# Microcontroller_board_Photodiode_plate.net
KiCad netlist of a schematic drawn in EasyEDA
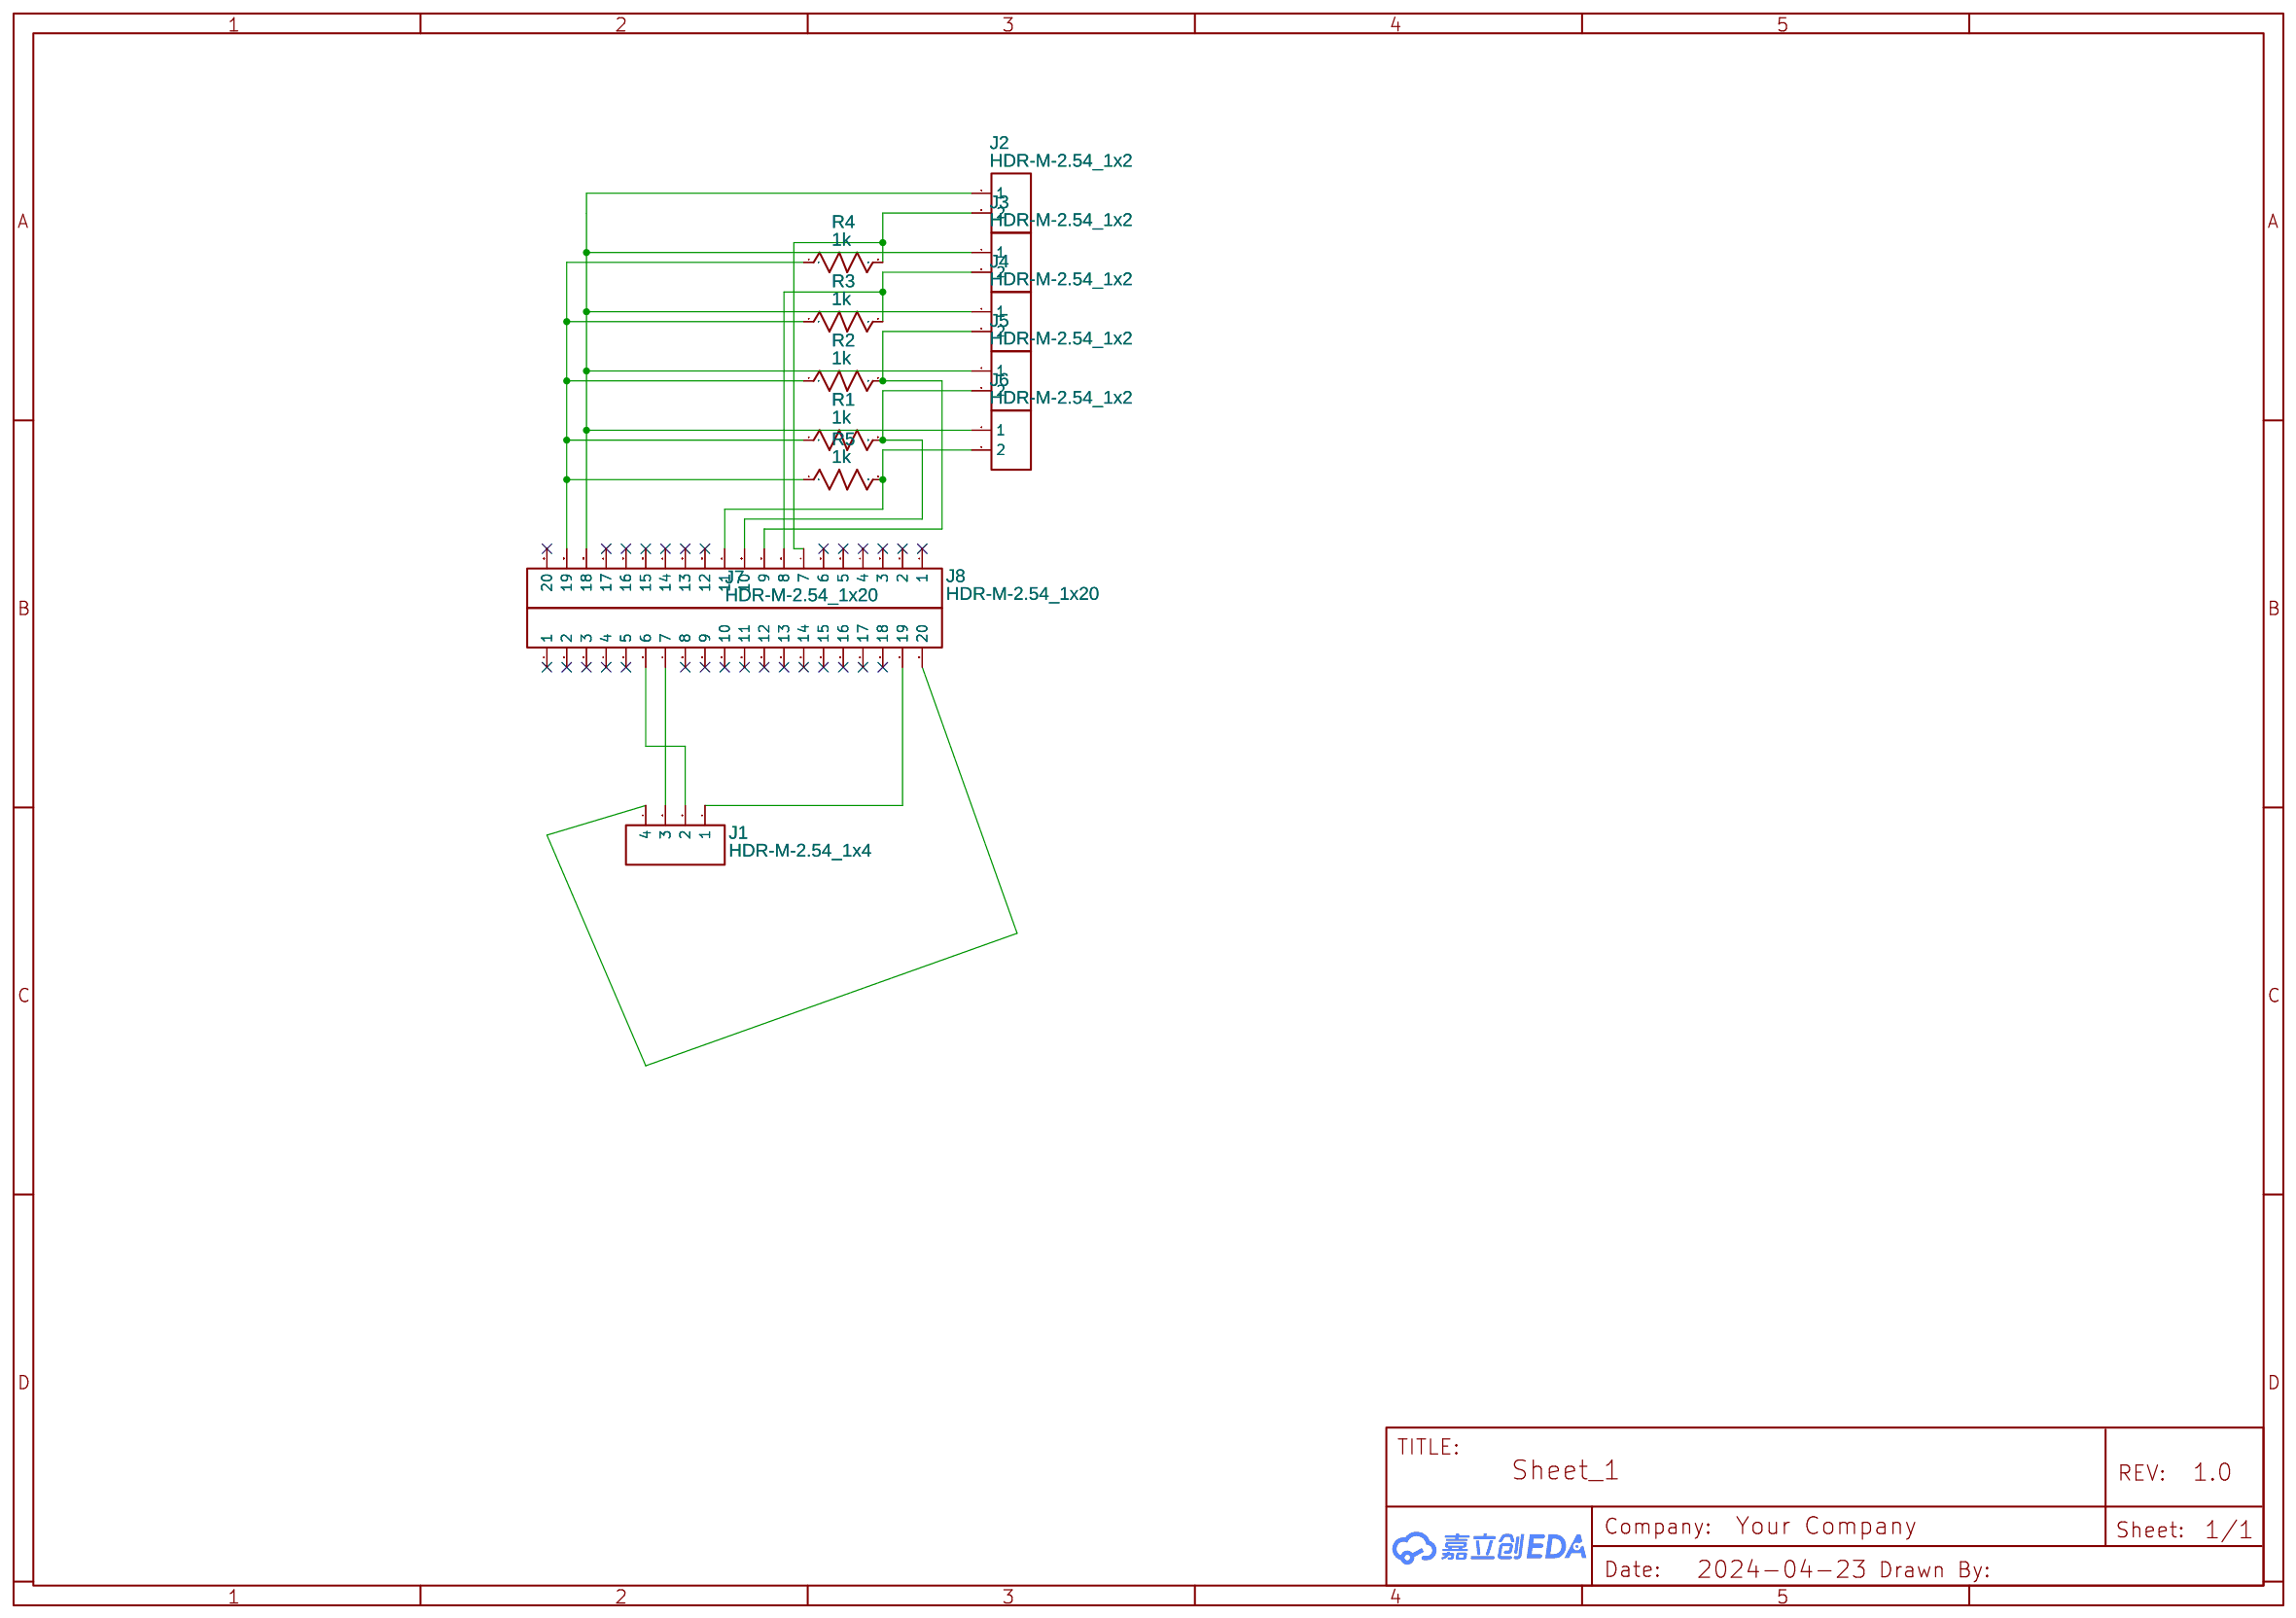
[diagram p0: schematic sheet]

(export (version "E")
  (design (tool "Eeschema 10.0.6"))
  (components
    (comp (ref "J1")
      (value "HDR-M-2.54_1x4")
      (fields (field (name "BOM_Supplier Part") "C124378"))
      (libsource (lib "") (part "HDR-M-2.54_1x4"))
    )
    (comp (ref "J2")
      (value "HDR-M-2.54_1x2")
      (fields (field (name "BOM_Supplier Part") "C124375"))
      (libsource (lib "") (part "HDR-M-2.54_1x2"))
    )
    (comp (ref "J3")
      (value "HDR-M-2.54_1x2")
      (fields (field (name "BOM_Supplier Part") "C124375"))
      (libsource (lib "") (part "HDR-M-2.54_1x2"))
    )
    (comp (ref "J4")
      (value "HDR-M-2.54_1x2")
      (fields (field (name "BOM_Supplier Part") "C124375"))
      (libsource (lib "") (part "HDR-M-2.54_1x2"))
    )
    (comp (ref "J5")
      (value "HDR-M-2.54_1x2")
      (fields (field (name "BOM_Supplier Part") "C124375"))
      (libsource (lib "") (part "HDR-M-2.54_1x2"))
    )
    (comp (ref "J6")
      (value "HDR-M-2.54_1x2")
      (fields (field (name "BOM_Supplier Part") "C124375"))
      (libsource (lib "") (part "HDR-M-2.54_1x2"))
    )
    (comp (ref "J7")
      (value "HDR-M-2.54_1x20")
      (fields (field (name "BOM_Supplier Part") "C50981"))
      (libsource (lib "") (part "HDR-M-2.54_1x20"))
    )
    (comp (ref "J8")
      (value "HDR-M-2.54_1x20")
      (fields (field (name "BOM_Supplier Part") "C50981"))
      (libsource (lib "") (part "HDR-M-2.54_1x20_1"))
    )
    (comp (ref "R1") (value "1k") (libsource (lib "") (part "R_AXIAL-0.4_US")))
    (comp (ref "R2") (value "1k") (libsource (lib "") (part "R_AXIAL-0.4_US")))
    (comp (ref "R3") (value "1k") (libsource (lib "") (part "R_AXIAL-0.4_US")))
    (comp (ref "R4") (value "1k") (libsource (lib "") (part "R_AXIAL-0.4_US")))
    (comp (ref "R5") (value "1k") (libsource (lib "") (part "R_AXIAL-0.4_US")))
  )
  (nets
    (net (code "1") (name "Net-(J1-Pad1)") (class "Default")
      (node (ref "J1") (pin "1") (pinfunction "1_1") (pintype "unspecified"))
      (node (ref "J7") (pin "19") (pinfunction "19_19") (pintype "unspecified"))
    )
    (net (code "2") (name "Net-(J1-Pad2)") (class "Default")
      (node (ref "J1") (pin "2") (pinfunction "2_2") (pintype "unspecified"))
      (node (ref "J7") (pin "6") (pinfunction "6_6") (pintype "unspecified"))
    )
    (net (code "3") (name "Net-(J1-Pad3)") (class "Default")
      (node (ref "J1") (pin "3") (pinfunction "3_3") (pintype "unspecified"))
      (node (ref "J7") (pin "7") (pinfunction "7_7") (pintype "unspecified"))
    )
    (net (code "4") (name "Net-(J1-Pad4)") (class "Default")
      (node (ref "J1") (pin "4") (pinfunction "4_4") (pintype "unspecified"))
      (node (ref "J7") (pin "20") (pinfunction "20_20") (pintype "unspecified"))
    )
    (net (code "5") (name "Net-(J2-Pad1)") (class "Default")
      (node (ref "J2") (pin "1") (pinfunction "1_1") (pintype "unspecified"))
      (node (ref "J3") (pin "1") (pinfunction "1_1") (pintype "unspecified"))
      (node (ref "J4") (pin "1") (pinfunction "1_1") (pintype "unspecified"))
      (node (ref "J5") (pin "1") (pinfunction "1_1") (pintype "unspecified"))
      (node (ref "J6") (pin "1") (pinfunction "1_1") (pintype "unspecified"))
      (node (ref "J8") (pin "18") (pinfunction "18_18") (pintype "unspecified"))
    )
    (net (code "6") (name "Net-(J2-Pad2)") (class "Default")
      (node (ref "J2") (pin "2") (pinfunction "2_2") (pintype "unspecified"))
      (node (ref "J8") (pin "7") (pinfunction "7_7") (pintype "unspecified"))
      (node (ref "R4") (pin "2") (pinfunction "2_2") (pintype "unspecified"))
    )
    (net (code "7") (name "Net-(J3-Pad2)") (class "Default")
      (node (ref "J3") (pin "2") (pinfunction "2_2") (pintype "unspecified"))
      (node (ref "J8") (pin "8") (pinfunction "8_8") (pintype "unspecified"))
      (node (ref "R3") (pin "2") (pinfunction "2_2") (pintype "unspecified"))
    )
    (net (code "8") (name "Net-(J4-Pad2)") (class "Default")
      (node (ref "J4") (pin "2") (pinfunction "2_2") (pintype "unspecified"))
      (node (ref "J8") (pin "9") (pinfunction "9_9") (pintype "unspecified"))
      (node (ref "R2") (pin "2") (pinfunction "2_2") (pintype "unspecified"))
    )
    (net (code "9") (name "Net-(J5-Pad2)") (class "Default")
      (node (ref "J5") (pin "2") (pinfunction "2_2") (pintype "unspecified"))
      (node (ref "J8") (pin "10") (pinfunction "10_10") (pintype "unspecified"))
      (node (ref "R1") (pin "2") (pinfunction "2_2") (pintype "unspecified"))
    )
    (net (code "10") (name "Net-(J6-Pad2)") (class "Default")
      (node (ref "J6") (pin "2") (pinfunction "2_2") (pintype "unspecified"))
      (node (ref "J8") (pin "11") (pinfunction "11_11") (pintype "unspecified"))
      (node (ref "R5") (pin "2") (pinfunction "2_2") (pintype "unspecified"))
    )
    (net (code "11") (name "Net-(J8-Pad19)") (class "Default")
      (node (ref "J8") (pin "19") (pinfunction "19_19") (pintype "unspecified"))
      (node (ref "R1") (pin "1") (pinfunction "1_1") (pintype "unspecified"))
      (node (ref "R2") (pin "1") (pinfunction "1_1") (pintype "unspecified"))
      (node (ref "R3") (pin "1") (pinfunction "1_1") (pintype "unspecified"))
      (node (ref "R4") (pin "1") (pinfunction "1_1") (pintype "unspecified"))
      (node (ref "R5") (pin "1") (pinfunction "1_1") (pintype "unspecified"))
    )
    (net (code "12") (name "unconnected-(J7-Pad1)") (class "Default")
      (node (ref "J7") (pin "1") (pinfunction "1_1") (pintype "unspecified+no_connect"))
    )
    (net (code "13") (name "unconnected-(J7-Pad2)") (class "Default")
      (node (ref "J7") (pin "2") (pinfunction "2_2") (pintype "unspecified+no_connect"))
    )
    (net (code "14") (name "unconnected-(J7-Pad3)") (class "Default")
      (node (ref "J7") (pin "3") (pinfunction "3_3") (pintype "unspecified+no_connect"))
    )
    (net (code "15") (name "unconnected-(J7-Pad4)") (class "Default")
      (node (ref "J7") (pin "4") (pinfunction "4_4") (pintype "unspecified+no_connect"))
    )
    (net (code "16") (name "unconnected-(J7-Pad5)") (class "Default")
      (node (ref "J7") (pin "5") (pinfunction "5_5") (pintype "unspecified+no_connect"))
    )
    (net (code "17") (name "unconnected-(J7-Pad8)") (class "Default")
      (node (ref "J7") (pin "8") (pinfunction "8_8") (pintype "unspecified+no_connect"))
    )
    (net (code "18") (name "unconnected-(J7-Pad9)") (class "Default")
      (node (ref "J7") (pin "9") (pinfunction "9_9") (pintype "unspecified+no_connect"))
    )
    (net (code "19") (name "unconnected-(J7-Pad10)") (class "Default")
      (node (ref "J7") (pin "10") (pinfunction "10_10") (pintype "unspecified+no_connect"))
    )
    (net (code "20") (name "unconnected-(J7-Pad11)") (class "Default")
      (node (ref "J7") (pin "11") (pinfunction "11_11") (pintype "unspecified+no_connect"))
    )
    (net (code "21") (name "unconnected-(J7-Pad12)") (class "Default")
      (node (ref "J7") (pin "12") (pinfunction "12_12") (pintype "unspecified+no_connect"))
    )
    (net (code "22") (name "unconnected-(J7-Pad13)") (class "Default")
      (node (ref "J7") (pin "13") (pinfunction "13_13") (pintype "unspecified+no_connect"))
    )
    (net (code "23") (name "unconnected-(J7-Pad14)") (class "Default")
      (node (ref "J7") (pin "14") (pinfunction "14_14") (pintype "unspecified+no_connect"))
    )
    (net (code "24") (name "unconnected-(J7-Pad15)") (class "Default")
      (node (ref "J7") (pin "15") (pinfunction "15_15") (pintype "unspecified+no_connect"))
    )
    (net (code "25") (name "unconnected-(J7-Pad16)") (class "Default")
      (node (ref "J7") (pin "16") (pinfunction "16_16") (pintype "unspecified+no_connect"))
    )
    (net (code "26") (name "unconnected-(J7-Pad17)") (class "Default")
      (node (ref "J7") (pin "17") (pinfunction "17_17") (pintype "unspecified+no_connect"))
    )
    (net (code "27") (name "unconnected-(J7-Pad18)") (class "Default")
      (node (ref "J7") (pin "18") (pinfunction "18_18") (pintype "unspecified+no_connect"))
    )
    (net (code "28") (name "unconnected-(J8-Pad1)") (class "Default")
      (node (ref "J8") (pin "1") (pinfunction "1_1") (pintype "unspecified+no_connect"))
    )
    (net (code "29") (name "unconnected-(J8-Pad2)") (class "Default")
      (node (ref "J8") (pin "2") (pinfunction "2_2") (pintype "unspecified+no_connect"))
    )
    (net (code "30") (name "unconnected-(J8-Pad3)") (class "Default")
      (node (ref "J8") (pin "3") (pinfunction "3_3") (pintype "unspecified+no_connect"))
    )
    (net (code "31") (name "unconnected-(J8-Pad4)") (class "Default")
      (node (ref "J8") (pin "4") (pinfunction "4_4") (pintype "unspecified+no_connect"))
    )
    (net (code "32") (name "unconnected-(J8-Pad5)") (class "Default")
      (node (ref "J8") (pin "5") (pinfunction "5_5") (pintype "unspecified+no_connect"))
    )
    (net (code "33") (name "unconnected-(J8-Pad6)") (class "Default")
      (node (ref "J8") (pin "6") (pinfunction "6_6") (pintype "unspecified+no_connect"))
    )
    (net (code "34") (name "unconnected-(J8-Pad12)") (class "Default")
      (node (ref "J8") (pin "12") (pinfunction "12_12") (pintype "unspecified+no_connect"))
    )
    (net (code "35") (name "unconnected-(J8-Pad13)") (class "Default")
      (node (ref "J8") (pin "13") (pinfunction "13_13") (pintype "unspecified+no_connect"))
    )
    (net (code "36") (name "unconnected-(J8-Pad14)") (class "Default")
      (node (ref "J8") (pin "14") (pinfunction "14_14") (pintype "unspecified+no_connect"))
    )
    (net (code "37") (name "unconnected-(J8-Pad15)") (class "Default")
      (node (ref "J8") (pin "15") (pinfunction "15_15") (pintype "unspecified+no_connect"))
    )
    (net (code "38") (name "unconnected-(J8-Pad16)") (class "Default")
      (node (ref "J8") (pin "16") (pinfunction "16_16") (pintype "unspecified+no_connect"))
    )
    (net (code "39") (name "unconnected-(J8-Pad17)") (class "Default")
      (node (ref "J8") (pin "17") (pinfunction "17_17") (pintype "unspecified+no_connect"))
    )
    (net (code "40") (name "unconnected-(J8-Pad20)") (class "Default")
      (node (ref "J8") (pin "20") (pinfunction "20_20") (pintype "unspecified+no_connect"))
    )
  )
)
